# led-tester.net
KiCad netlist of a schematic drawn in EAGLE
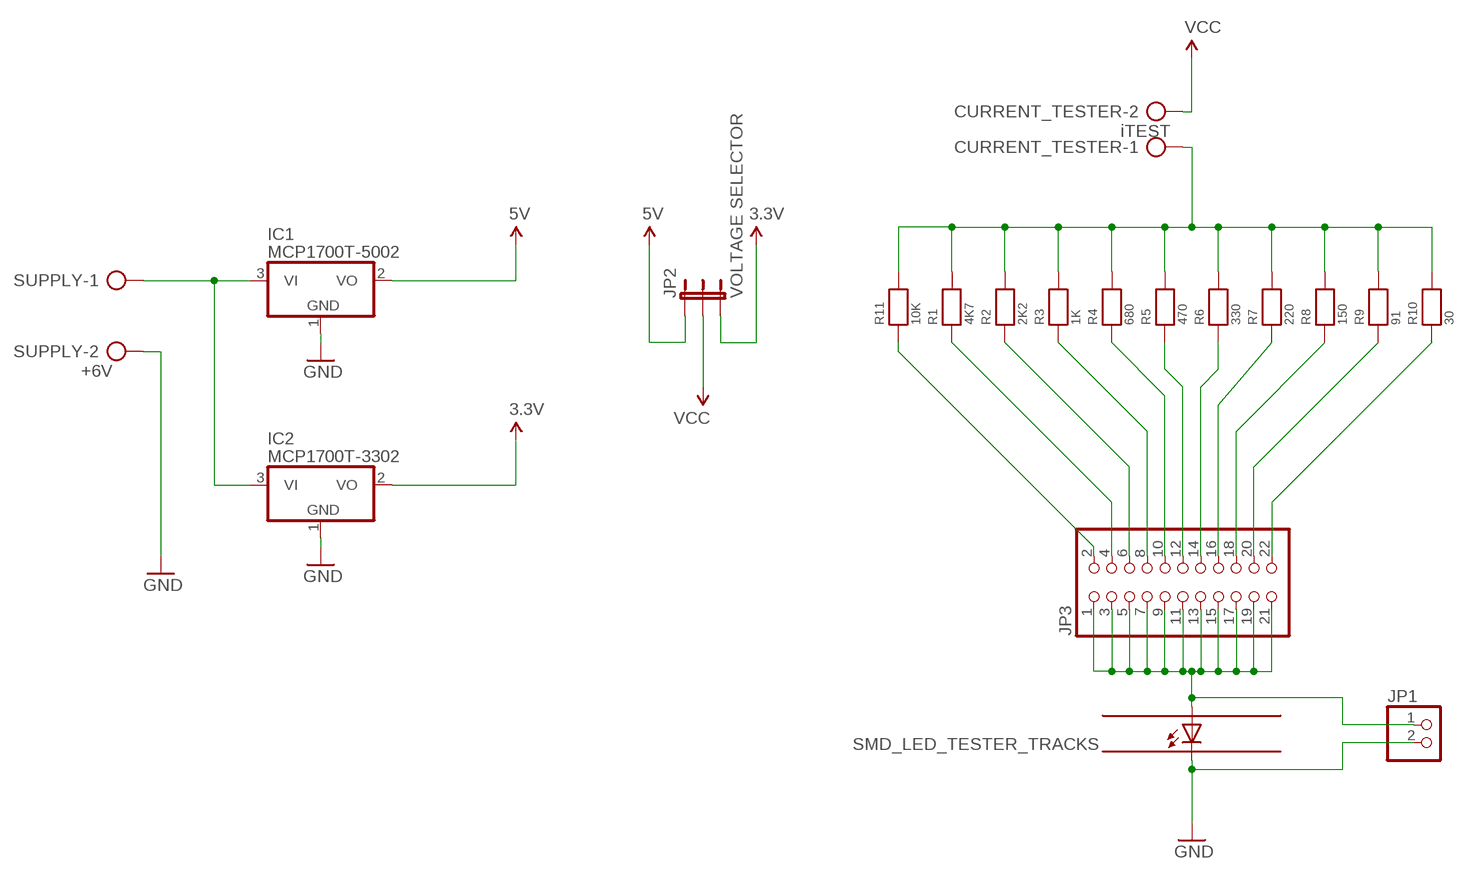
[diagram p0: schematic, sheet 1]

(export (version "E")
  (design (tool "Eeschema 10.0.6"))
  (components
    (comp (ref "CURRENT_TESTER")
      (value "iTEST")
      (footprint "eagle-import:TERMINAL_BLOCK_X2")
      (libsource (lib "eagle-import") (part "TERMINAL_BLOCK_X2"))
    )
    (comp (ref "IC1")
      (value "MCP1700T-5002")
      (footprint "eagle-import:SOT23")
      (libsource (lib "eagle-import") (part "MCP1703CB"))
    )
    (comp (ref "IC2")
      (value "MCP1700T-3302")
      (footprint "eagle-import:SOT23")
      (libsource (lib "eagle-import") (part "MCP1703CB"))
    )
    (comp (ref "JP1")
      (value "PINHD-1X2")
      (footprint "eagle-import:1X02")
      (libsource (lib "eagle-import") (part "PINHD-1X2"))
    )
    (comp (ref "JP2")
      (value "VOLTAGE SELECTOR")
      (footprint "eagle-import:1X03")
      (libsource (lib "eagle-import") (part "JUMPER-3PTH"))
    )
    (comp (ref "JP3")
      (value "PINHD-2X11")
      (footprint "eagle-import:2X11")
      (libsource (lib "eagle-import") (part "PINHD-2X11"))
    )
    (comp (ref "R1")
      (value "4K7")
      (footprint "eagle-import:0805")
      (libsource (lib "eagle-import") (part "RESISTOR0805"))
    )
    (comp (ref "R2")
      (value "2K2")
      (footprint "eagle-import:0805")
      (libsource (lib "eagle-import") (part "RESISTOR0805"))
    )
    (comp (ref "R3")
      (value "1K")
      (footprint "eagle-import:0805")
      (libsource (lib "eagle-import") (part "RESISTOR0805"))
    )
    (comp (ref "R4")
      (value "680")
      (footprint "eagle-import:0805")
      (libsource (lib "eagle-import") (part "RESISTOR0805"))
    )
    (comp (ref "R5")
      (value "470")
      (footprint "eagle-import:0805")
      (libsource (lib "eagle-import") (part "RESISTOR0805"))
    )
    (comp (ref "R6")
      (value "330")
      (footprint "eagle-import:0805")
      (libsource (lib "eagle-import") (part "RESISTOR0805"))
    )
    (comp (ref "R7")
      (value "220")
      (footprint "eagle-import:0805")
      (libsource (lib "eagle-import") (part "RESISTOR0805"))
    )
    (comp (ref "R8")
      (value "150")
      (footprint "eagle-import:0805")
      (libsource (lib "eagle-import") (part "RESISTOR0805"))
    )
    (comp (ref "R9")
      (value "91")
      (footprint "eagle-import:0805")
      (libsource (lib "eagle-import") (part "RESISTOR0805"))
    )
    (comp (ref "R10")
      (value "30")
      (footprint "eagle-import:0805")
      (libsource (lib "eagle-import") (part "RESISTOR0805"))
    )
    (comp (ref "R11")
      (value "10K")
      (footprint "eagle-import:0805")
      (libsource (lib "eagle-import") (part "RESISTOR0805"))
    )
    (comp (ref "SUPPLY")
      (value "+6V")
      (footprint "eagle-import:TERMINAL_BLOCK_X2")
      (libsource (lib "eagle-import") (part "TERMINAL_BLOCK_X2"))
    )
    (comp (ref "U$1")
      (value "SMD_LED_TESTER_TRACKS")
      (footprint "eagle-import:SMD_LED_TESTER_TRACKS")
      (libsource (lib "eagle-import") (part "SMD_LED_TESTER_TRACKS"))
    )
  )
  (nets
    (net (code "1") (name "3.3V") (class "Default")
      (node (ref "IC2") (pin "2") (pinfunction "VO_2") (pintype "passive"))
      (node (ref "JP2") (pin "3") (pinfunction "3_3") (pintype "passive"))
    )
    (net (code "2") (name "5V") (class "Default")
      (node (ref "IC1") (pin "2") (pinfunction "VO_2") (pintype "passive"))
      (node (ref "JP2") (pin "1") (pinfunction "1_1") (pintype "passive"))
    )
    (net (code "3") (name "GND") (class "Default")
      (node (ref "IC1") (pin "1") (pinfunction "GND_1") (pintype "passive"))
      (node (ref "IC2") (pin "1") (pinfunction "GND_1") (pintype "passive"))
      (node (ref "JP1") (pin "2") (pinfunction "2_2") (pintype "passive"))
      (node (ref "SUPPLY") (pin "2") (pinfunction "KL_2") (pintype "passive"))
      (node (ref "U$1") (pin "P$2") (pinfunction "C_P$2") (pintype "passive"))
    )
    (net (code "4") (name "Net-(CURRENT_TESTERA-KL)") (class "Default")
      (node (ref "CURRENT_TESTER") (pin "1") (pinfunction "KL_1") (pintype "passive"))
      (node (ref "R1") (pin "2") (pinfunction "2_2") (pintype "passive"))
      (node (ref "R10") (pin "2") (pinfunction "2_2") (pintype "passive"))
      (node (ref "R11") (pin "2") (pinfunction "2_2") (pintype "passive"))
      (node (ref "R2") (pin "2") (pinfunction "2_2") (pintype "passive"))
      (node (ref "R3") (pin "2") (pinfunction "2_2") (pintype "passive"))
      (node (ref "R4") (pin "2") (pinfunction "2_2") (pintype "passive"))
      (node (ref "R5") (pin "2") (pinfunction "2_2") (pintype "passive"))
      (node (ref "R6") (pin "2") (pinfunction "2_2") (pintype "passive"))
      (node (ref "R7") (pin "2") (pinfunction "2_2") (pintype "passive"))
      (node (ref "R8") (pin "2") (pinfunction "2_2") (pintype "passive"))
      (node (ref "R9") (pin "2") (pinfunction "2_2") (pintype "passive"))
    )
    (net (code "5") (name "Net-(IC1-VI)") (class "Default")
      (node (ref "IC1") (pin "3") (pinfunction "VI_3") (pintype "input"))
      (node (ref "IC2") (pin "3") (pinfunction "VI_3") (pintype "input"))
      (node (ref "SUPPLY") (pin "1") (pinfunction "KL_1") (pintype "passive"))
    )
    (net (code "6") (name "Net-(JP3-Pad2)") (class "Default")
      (node (ref "JP3") (pin "2") (pinfunction "2_2") (pintype "passive"))
      (node (ref "R11") (pin "1") (pinfunction "1_1") (pintype "passive"))
    )
    (net (code "7") (name "Net-(JP3-Pad4)") (class "Default")
      (node (ref "JP3") (pin "4") (pinfunction "4_4") (pintype "passive"))
      (node (ref "R1") (pin "1") (pinfunction "1_1") (pintype "passive"))
    )
    (net (code "8") (name "Net-(JP3-Pad6)") (class "Default")
      (node (ref "JP3") (pin "6") (pinfunction "6_6") (pintype "passive"))
      (node (ref "R2") (pin "1") (pinfunction "1_1") (pintype "passive"))
    )
    (net (code "9") (name "Net-(JP3-Pad8)") (class "Default")
      (node (ref "JP3") (pin "8") (pinfunction "8_8") (pintype "passive"))
      (node (ref "R3") (pin "1") (pinfunction "1_1") (pintype "passive"))
    )
    (net (code "10") (name "Net-(JP3-Pad10)") (class "Default")
      (node (ref "JP3") (pin "10") (pinfunction "10_10") (pintype "passive"))
      (node (ref "R4") (pin "1") (pinfunction "1_1") (pintype "passive"))
    )
    (net (code "11") (name "Net-(JP3-Pad12)") (class "Default")
      (node (ref "JP3") (pin "12") (pinfunction "12_12") (pintype "passive"))
      (node (ref "R5") (pin "1") (pinfunction "1_1") (pintype "passive"))
    )
    (net (code "12") (name "Net-(JP3-Pad14)") (class "Default")
      (node (ref "JP3") (pin "14") (pinfunction "14_14") (pintype "passive"))
      (node (ref "R6") (pin "1") (pinfunction "1_1") (pintype "passive"))
    )
    (net (code "13") (name "Net-(JP3-Pad16)") (class "Default")
      (node (ref "JP3") (pin "16") (pinfunction "16_16") (pintype "passive"))
      (node (ref "R7") (pin "1") (pinfunction "1_1") (pintype "passive"))
    )
    (net (code "14") (name "Net-(JP3-Pad18)") (class "Default")
      (node (ref "JP3") (pin "18") (pinfunction "18_18") (pintype "passive"))
      (node (ref "R8") (pin "1") (pinfunction "1_1") (pintype "passive"))
    )
    (net (code "15") (name "Net-(JP3-Pad20)") (class "Default")
      (node (ref "JP3") (pin "20") (pinfunction "20_20") (pintype "passive"))
      (node (ref "R9") (pin "1") (pinfunction "1_1") (pintype "passive"))
    )
    (net (code "16") (name "Net-(JP3-Pad22)") (class "Default")
      (node (ref "JP3") (pin "22") (pinfunction "22_22") (pintype "passive"))
      (node (ref "R10") (pin "1") (pinfunction "1_1") (pintype "passive"))
    )
    (net (code "17") (name "Net-(U$1-A)") (class "Default")
      (node (ref "JP1") (pin "1") (pinfunction "1_1") (pintype "passive"))
      (node (ref "JP3") (pin "1") (pinfunction "1_1") (pintype "passive"))
      (node (ref "JP3") (pin "11") (pinfunction "11_11") (pintype "passive"))
      (node (ref "JP3") (pin "13") (pinfunction "13_13") (pintype "passive"))
      (node (ref "JP3") (pin "15") (pinfunction "15_15") (pintype "passive"))
      (node (ref "JP3") (pin "17") (pinfunction "17_17") (pintype "passive"))
      (node (ref "JP3") (pin "19") (pinfunction "19_19") (pintype "passive"))
      (node (ref "JP3") (pin "21") (pinfunction "21_21") (pintype "passive"))
      (node (ref "JP3") (pin "3") (pinfunction "3_3") (pintype "passive"))
      (node (ref "JP3") (pin "5") (pinfunction "5_5") (pintype "passive"))
      (node (ref "JP3") (pin "7") (pinfunction "7_7") (pintype "passive"))
      (node (ref "JP3") (pin "9") (pinfunction "9_9") (pintype "passive"))
      (node (ref "U$1") (pin "P$1") (pinfunction "A_P$1") (pintype "passive"))
    )
    (net (code "18") (name "VCC") (class "Default")
      (node (ref "CURRENT_TESTER") (pin "2") (pinfunction "KL_2") (pintype "passive"))
      (node (ref "JP2") (pin "2") (pinfunction "2_2") (pintype "passive"))
    )
  )
)
